# SCH_Extension-Platine-Relais-ESP32-Veth_.net
KiCad netlist of a schematic drawn in EasyEDA
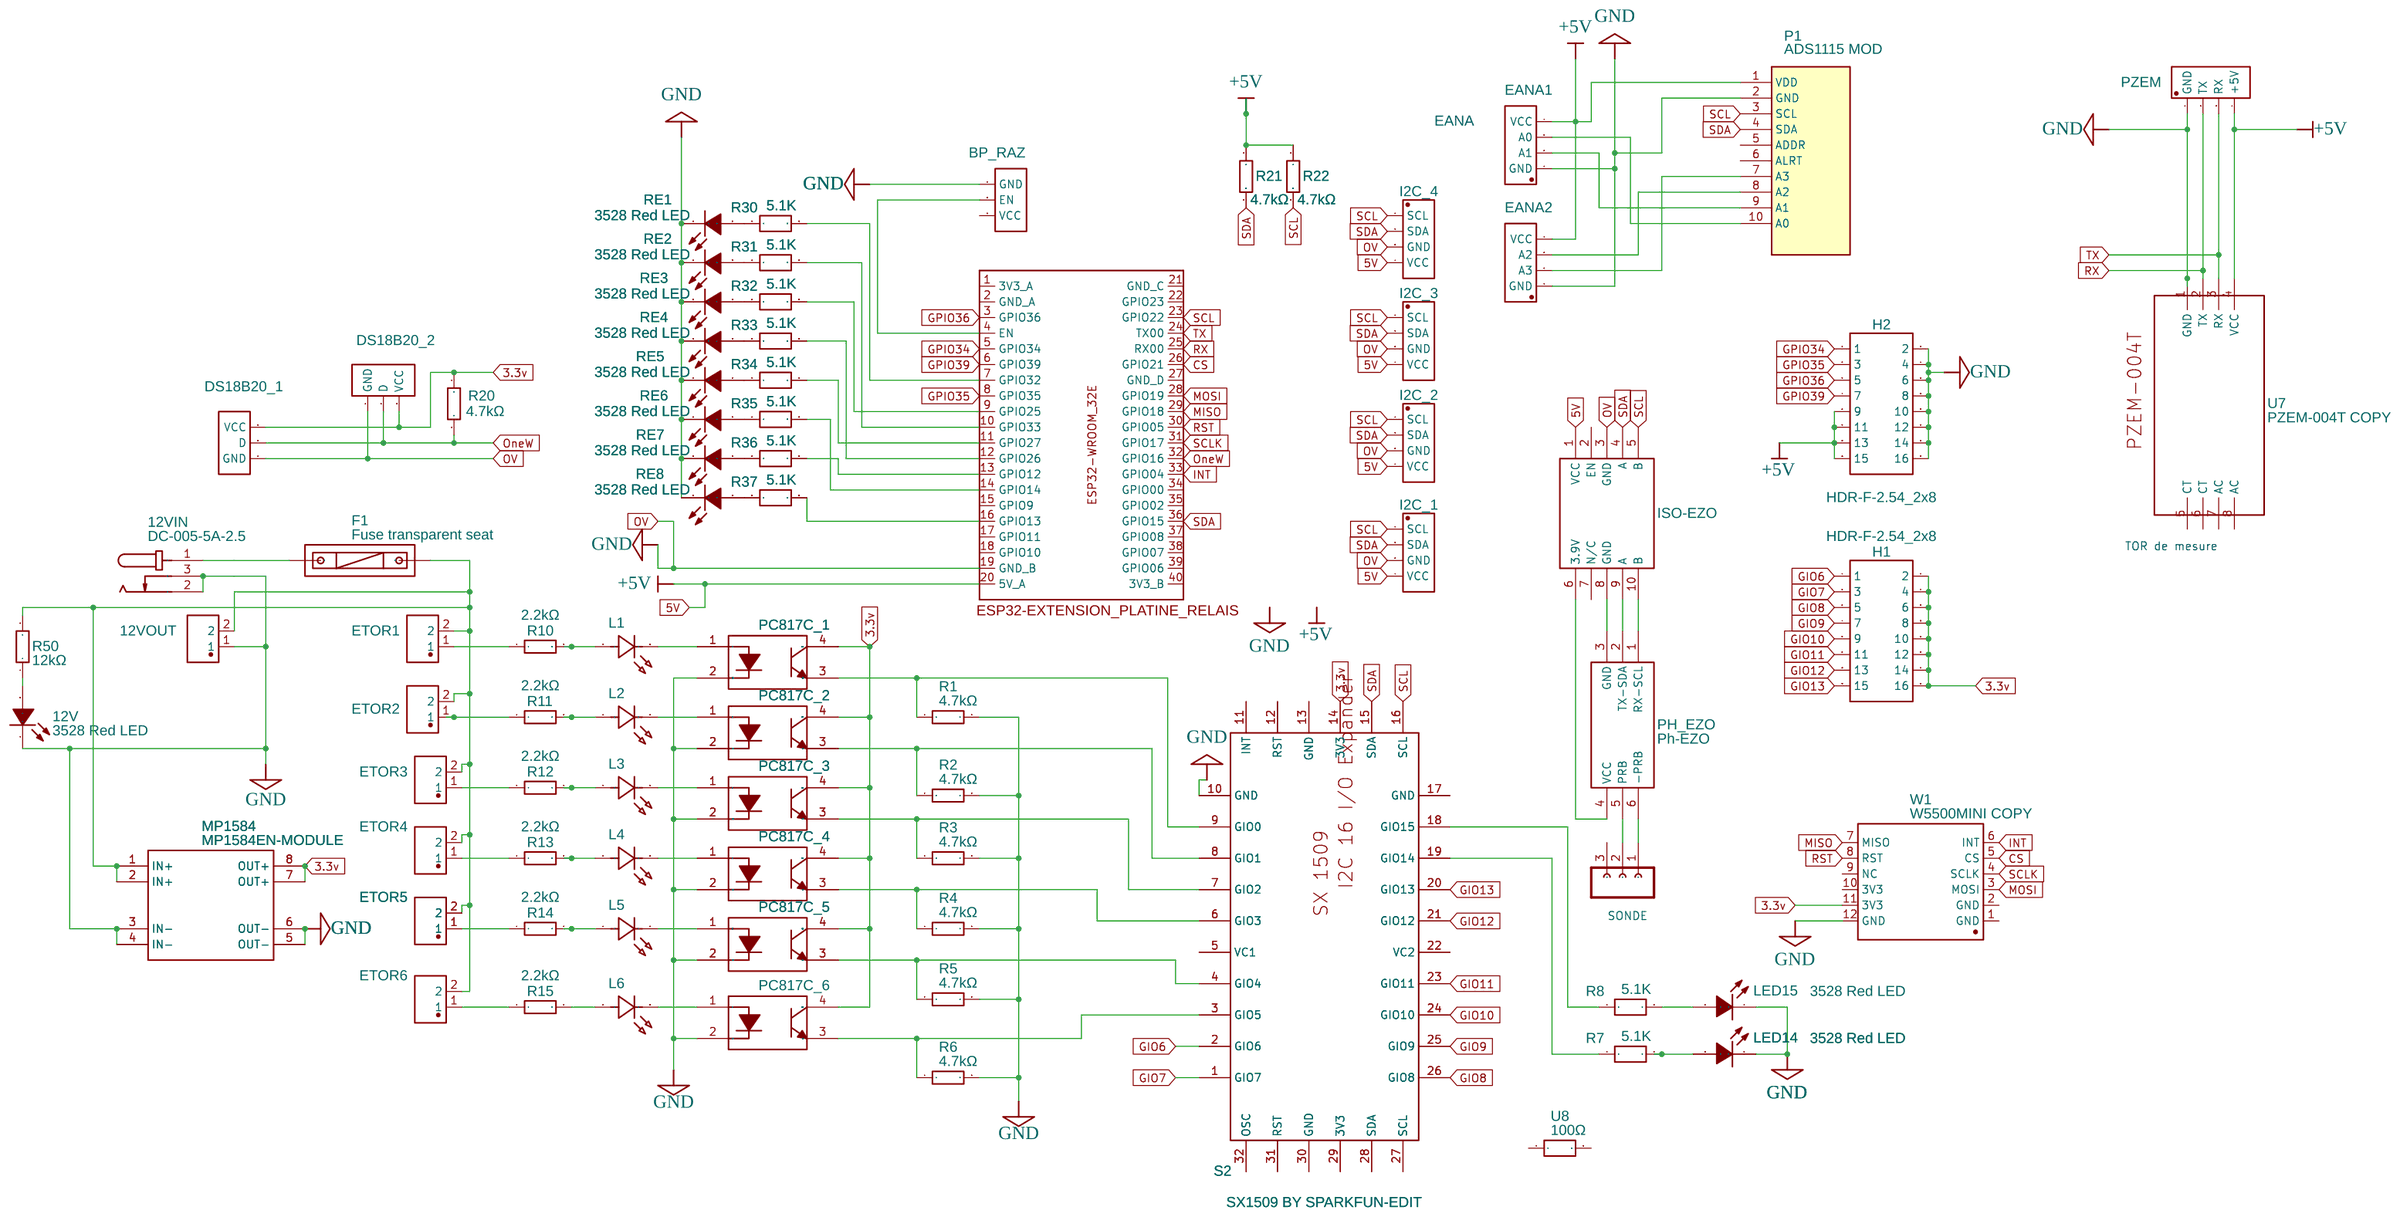
[diagram p0: schematic sheet]

(export (version "E")
  (design (tool "Eeschema 10.0.6"))
  (components
    (comp (ref "12V")
      (value "3528 Red LED")
      (fields (field (name "Manufacturer Part") "3528R (SMT业务专用)"))
      (libsource (lib "") (part "3528 Red LED_2"))
    )
    (comp (ref "12VIN")
      (value "DC-005-5A-2.5")
      (fields (field (name "Manufacturer") "XKB Connectivity(中国星坤)"))
      (libsource (lib "") (part "DC-005-5A-2.5"))
    )
    (comp (ref "12VOUT")
      (value "12V1")
      (fields
        (field (name "Manufacturer Part") "DB128L-5.08-2P-GN-S")
        (field (name "Manufacturer") "DORABO(地博电气)")
      )
      (libsource (lib "") (part "DB128L-5.08-2P_1"))
    )
    (comp (ref "BP_RAZ")
      (value "RAZ")
      (fields (field (name "Manufacturer Part") "Header2.54mm 1*3P") (field (name "Manufacturer") "BOOMELE"))
      (libsource (lib "") (part "Unknown_190_-515"))
    )
    (comp (ref "DS18B20_1")
      (value "DS18B20_1")
      (fields (field (name "Manufacturer Part") "Header2.54mm 1*3P") (field (name "Manufacturer") "BOOMELE"))
      (libsource (lib "") (part "Unknown_-295_-360"))
    )
    (comp (ref "DS18B20_2")
      (value "DS18B20_2")
      (fields (field (name "Manufacturer Part") "Header2.54mm 1*3P") (field (name "Manufacturer") "BOOMELE"))
      (libsource (lib "") (part "Unknown_-205_-395"))
    )
    (comp (ref "EANA1")
      (value "I2C_2")
      (fields
        (field (name "Manufacturer Part") "210S-1*4P L=11.6MMGold-plated black")
        (field (name "Manufacturer") "Ckmtw")
      )
      (libsource (lib "") (part "Unknown_525_-550"))
    )
    (comp (ref "EANA2")
      (value "I2C_2")
      (fields
        (field (name "Manufacturer Part") "210S-1*4P L=11.6MMGold-plated black")
        (field (name "Manufacturer") "Ckmtw")
      )
      (libsource (lib "") (part "Unknown_525_-475"))
    )
    (comp (ref "ETOR1")
      (value "ETOR1")
      (fields
        (field (name "Manufacturer Part") "DB128L-5.08-2P-GN-S")
        (field (name "Manufacturer") "DORABO(地博电气)")
      )
      (libsource (lib "") (part "DB128L-5.08-2P"))
    )
    (comp (ref "ETOR2")
      (value "ETOR1")
      (fields
        (field (name "Manufacturer Part") "DB128L-5.08-2P-GN-S")
        (field (name "Manufacturer") "DORABO(地博电气)")
      )
      (libsource (lib "") (part "DB128L-5.08-2P"))
    )
    (comp (ref "ETOR3")
      (value "ETOR1")
      (fields
        (field (name "Manufacturer Part") "DB128L-5.08-2P-GN-S")
        (field (name "Manufacturer") "DORABO(地博电气)")
      )
      (libsource (lib "") (part "DB128L-5.08-2P"))
    )
    (comp (ref "ETOR4")
      (value "ETOR1")
      (fields
        (field (name "Manufacturer Part") "DB128L-5.08-2P-GN-S")
        (field (name "Manufacturer") "DORABO(地博电气)")
      )
      (libsource (lib "") (part "DB128L-5.08-2P"))
    )
    (comp (ref "ETOR5")
      (value "ETOR1")
      (fields
        (field (name "Manufacturer Part") "DB128L-5.08-2P-GN-S")
        (field (name "Manufacturer") "DORABO(地博电气)")
      )
      (libsource (lib "") (part "DB128L-5.08-2P"))
    )
    (comp (ref "ETOR6")
      (value "ETOR1")
      (fields
        (field (name "Manufacturer Part") "DB128L-5.08-2P-GN-S")
        (field (name "Manufacturer") "DORABO(地博电气)")
      )
      (libsource (lib "") (part "DB128L-5.08-2P"))
    )
    (comp (ref "F1")
      (value "Fuse transparent seat")
      (fields (field (name "Manufacturer Part") "保险丝透明座") (field (name "Manufacturer") "xcfuse(旭程)"))
      (libsource (lib "") (part "Fuse transparent seat"))
    )
    (comp (ref "H1") (value "HDR-F-2.54_2x8") (libsource (lib "") (part "HDR-F-2.54_2x8")))
    (comp (ref "H2") (value "HDR-F-2.54_2x8") (libsource (lib "") (part "HDR-F-2.54_2x8")))
    (comp (ref "I2C_1")
      (value "I2C_2")
      (fields
        (field (name "Manufacturer Part") "210S-1*4P L=11.6MMGold-plated black")
        (field (name "Manufacturer") "Ckmtw")
      )
      (libsource (lib "") (part "Unknown_450_-290"))
    )
    (comp (ref "I2C_2")
      (value "I2C_2")
      (fields
        (field (name "Manufacturer Part") "210S-1*4P L=11.6MMGold-plated black")
        (field (name "Manufacturer") "Ckmtw")
      )
      (libsource (lib "") (part "Unknown_450_-360"))
    )
    (comp (ref "I2C_3")
      (value "I2C_2")
      (fields
        (field (name "Manufacturer Part") "210S-1*4P L=11.6MMGold-plated black")
        (field (name "Manufacturer") "Ckmtw")
      )
      (libsource (lib "") (part "Unknown_450_-425"))
    )
    (comp (ref "I2C_4")
      (value "I2C_2")
      (fields
        (field (name "Manufacturer Part") "210S-1*4P L=11.6MMGold-plated black")
        (field (name "Manufacturer") "Ckmtw")
      )
      (libsource (lib "") (part "Unknown_450_-490"))
    )
    (comp (ref "ISO-EZO") (value "EZO-PH-ISOLATOR") (libsource (lib "") (part "EZO-PH-ISOLATOR")))
    (comp (ref "L1")
      (value "HLMP-4700")
      (fields (field (name "Manufacturer") "Broadcom/AVAGO(安华高)"))
      (libsource (lib "") (part "HLMP-4700"))
    )
    (comp (ref "L2")
      (value "HLMP-4700")
      (fields (field (name "Manufacturer") "Broadcom/AVAGO(安华高)"))
      (libsource (lib "") (part "HLMP-4700"))
    )
    (comp (ref "L3")
      (value "HLMP-4700")
      (fields (field (name "Manufacturer") "Broadcom/AVAGO(安华高)"))
      (libsource (lib "") (part "HLMP-4700"))
    )
    (comp (ref "L4")
      (value "HLMP-4700")
      (fields (field (name "Manufacturer") "Broadcom/AVAGO(安华高)"))
      (libsource (lib "") (part "HLMP-4700"))
    )
    (comp (ref "L5")
      (value "HLMP-4700")
      (fields (field (name "Manufacturer") "Broadcom/AVAGO(安华高)"))
      (libsource (lib "") (part "HLMP-4700"))
    )
    (comp (ref "L6")
      (value "HLMP-4700")
      (fields (field (name "Manufacturer") "Broadcom/AVAGO(安华高)"))
      (libsource (lib "") (part "HLMP-4700"))
    )
    (comp (ref "LED14")
      (value "3528 Red LED")
      (fields (field (name "Manufacturer Part") "3528R (SMT业务专用)"))
      (libsource (lib "") (part "3528 Red LED_1"))
    )
    (comp (ref "LED15")
      (value "3528 Red LED")
      (fields (field (name "Manufacturer Part") "3528R (SMT业务专用)"))
      (libsource (lib "") (part "3528 Red LED_1"))
    )
    (comp (ref "MP1584") (value "MP1584EN-MODULE") (libsource (lib "") (part "MP1584EN-MODULE")))
    (comp (ref "P1") (value "ADS1115 MOD") (libsource (lib "") (part "ADS1115 MOD")))
    (comp (ref "PH_EZO") (value "Ph-EZO") (libsource (lib "") (part "EC-EZO")))
    (comp (ref "PZEM")
      (value "I2C_2")
      (fields
        (field (name "Manufacturer Part") "210S-1*4P L=11.6MMGold-plated black")
        (field (name "Manufacturer") "Ckmtw")
      )
      (libsource (lib "") (part "Unknown_960_-585"))
    )
    (comp (ref "R1")
      (value "4.7kΩ")
      (fields
        (field (name "Manufacturer Part") "MFR0W8F4701A50")
        (field (name "Manufacturer") "UNI-ROYAL(厚声)")
      )
      (libsource (lib "") (part "MFR0W8F4701A50"))
    )
    (comp (ref "R2")
      (value "4.7kΩ")
      (fields
        (field (name "Manufacturer Part") "MFR0W8F4701A50")
        (field (name "Manufacturer") "UNI-ROYAL(厚声)")
      )
      (libsource (lib "") (part "MFR0W8F4701A50"))
    )
    (comp (ref "R3")
      (value "4.7kΩ")
      (fields
        (field (name "Manufacturer Part") "MFR0W8F4701A50")
        (field (name "Manufacturer") "UNI-ROYAL(厚声)")
      )
      (libsource (lib "") (part "MFR0W8F4701A50"))
    )
    (comp (ref "R4")
      (value "4.7kΩ")
      (fields
        (field (name "Manufacturer Part") "MFR0W8F4701A50")
        (field (name "Manufacturer") "UNI-ROYAL(厚声)")
      )
      (libsource (lib "") (part "MFR0W8F4701A50"))
    )
    (comp (ref "R5")
      (value "4.7kΩ")
      (fields
        (field (name "Manufacturer Part") "MFR0W8F4701A50")
        (field (name "Manufacturer") "UNI-ROYAL(厚声)")
      )
      (libsource (lib "") (part "MFR0W8F4701A50"))
    )
    (comp (ref "R6")
      (value "4.7kΩ")
      (fields
        (field (name "Manufacturer Part") "MFR0W8F4701A50")
        (field (name "Manufacturer") "UNI-ROYAL(厚声)")
      )
      (libsource (lib "") (part "MFR0W8F4701A50"))
    )
    (comp (ref "R7") (value "5.1K") (libsource (lib "") (part "R_1206_EU")))
    (comp (ref "R8") (value "5.1K") (libsource (lib "") (part "R_1206_EU")))
    (comp (ref "R10")
      (value "2.2kΩ")
      (fields
        (field (name "Manufacturer Part") "MFR0W8F2201A50")
        (field (name "Manufacturer") "UNI-ROYAL(厚声)")
      )
      (libsource (lib "") (part "MFR0W8F2201A50"))
    )
    (comp (ref "R11")
      (value "2.2kΩ")
      (fields
        (field (name "Manufacturer Part") "MFR0W8F2201A50")
        (field (name "Manufacturer") "UNI-ROYAL(厚声)")
      )
      (libsource (lib "") (part "MFR0W8F2201A50"))
    )
    (comp (ref "R12")
      (value "2.2kΩ")
      (fields
        (field (name "Manufacturer Part") "MFR0W8F2201A50")
        (field (name "Manufacturer") "UNI-ROYAL(厚声)")
      )
      (libsource (lib "") (part "MFR0W8F2201A50"))
    )
    (comp (ref "R13")
      (value "2.2kΩ")
      (fields
        (field (name "Manufacturer Part") "MFR0W8F2201A50")
        (field (name "Manufacturer") "UNI-ROYAL(厚声)")
      )
      (libsource (lib "") (part "MFR0W8F2201A50"))
    )
    (comp (ref "R14")
      (value "2.2kΩ")
      (fields
        (field (name "Manufacturer Part") "MFR0W8F2201A50")
        (field (name "Manufacturer") "UNI-ROYAL(厚声)")
      )
      (libsource (lib "") (part "MFR0W8F2201A50"))
    )
    (comp (ref "R15")
      (value "2.2kΩ")
      (fields
        (field (name "Manufacturer Part") "MFR0W8F2201A50")
        (field (name "Manufacturer") "UNI-ROYAL(厚声)")
      )
      (libsource (lib "") (part "MFR0W8F2201A50"))
    )
    (comp (ref "R20")
      (value "4.7kΩ")
      (fields
        (field (name "Manufacturer Part") "MFR0W8F4701A50")
        (field (name "Manufacturer") "UNI-ROYAL(厚声)")
      )
      (libsource (lib "") (part "MFR0W8F4701A50_1"))
    )
    (comp (ref "R21")
      (value "4.7kΩ")
      (fields
        (field (name "Manufacturer Part") "MFR0W8F4701A50")
        (field (name "Manufacturer") "UNI-ROYAL(厚声)")
      )
      (libsource (lib "") (part "MFR0W8F4701A50_1"))
    )
    (comp (ref "R22")
      (value "4.7kΩ")
      (fields
        (field (name "Manufacturer Part") "MFR0W8F4701A50")
        (field (name "Manufacturer") "UNI-ROYAL(厚声)")
      )
      (libsource (lib "") (part "MFR0W8F4701A50_1"))
    )
    (comp (ref "R30") (value "5.1K") (libsource (lib "") (part "R_1206_EU")))
    (comp (ref "R31") (value "5.1K") (libsource (lib "") (part "R_1206_EU")))
    (comp (ref "R32") (value "5.1K") (libsource (lib "") (part "R_1206_EU")))
    (comp (ref "R33") (value "5.1K") (libsource (lib "") (part "R_1206_EU")))
    (comp (ref "R34") (value "5.1K") (libsource (lib "") (part "R_1206_EU")))
    (comp (ref "R35") (value "5.1K") (libsource (lib "") (part "R_1206_EU")))
    (comp (ref "R36") (value "5.1K") (libsource (lib "") (part "R_1206_EU")))
    (comp (ref "R37") (value "5.1K") (libsource (lib "") (part "R_1206_EU")))
    (comp (ref "R50")
      (value "12kΩ")
      (fields
        (field (name "Manufacturer Part") "MFR0W8F2201A50")
        (field (name "Manufacturer") "UNI-ROYAL(厚声)")
      )
      (libsource (lib "") (part "MFR0W8F2201A50_1"))
    )
    (comp (ref "RE1")
      (value "3528 Red LED")
      (fields (field (name "Manufacturer Part") "3528R (SMT业务专用)"))
      (libsource (lib "") (part "3528 Red LED"))
    )
    (comp (ref "RE2")
      (value "3528 Red LED")
      (fields (field (name "Manufacturer Part") "3528R (SMT业务专用)"))
      (libsource (lib "") (part "3528 Red LED"))
    )
    (comp (ref "RE3")
      (value "3528 Red LED")
      (fields (field (name "Manufacturer Part") "3528R (SMT业务专用)"))
      (libsource (lib "") (part "3528 Red LED"))
    )
    (comp (ref "RE4")
      (value "3528 Red LED")
      (fields (field (name "Manufacturer Part") "3528R (SMT业务专用)"))
      (libsource (lib "") (part "3528 Red LED"))
    )
    (comp (ref "RE5")
      (value "3528 Red LED")
      (fields (field (name "Manufacturer Part") "3528R (SMT业务专用)"))
      (libsource (lib "") (part "3528 Red LED"))
    )
    (comp (ref "RE6")
      (value "3528 Red LED")
      (fields (field (name "Manufacturer Part") "3528R (SMT业务专用)"))
      (libsource (lib "") (part "3528 Red LED"))
    )
    (comp (ref "RE7")
      (value "3528 Red LED")
      (fields (field (name "Manufacturer Part") "3528R (SMT业务专用)"))
      (libsource (lib "") (part "3528 Red LED"))
    )
    (comp (ref "RE8")
      (value "3528 Red LED")
      (fields (field (name "Manufacturer Part") "3528R (SMT业务专用)"))
      (libsource (lib "") (part "3528 Red LED"))
    )
    (comp (ref "S2")
      (value "SX1509 BY SPARKFUN-EDIT")
      (fields (field (name "Manufacturer Part") "SX1509") (field (name "Manufacturer") "SPARkFUN"))
      (libsource (lib "") (part "SX1509 BY SPARKFUN-EDIT"))
    )
    (comp (ref "SONDE") (value "FE03-1\"") (libsource (lib "") (part "Unknown_585_-75")))
    (comp (ref "U$1") (value "ESP32-PLATINE_RELAIS") (libsource (lib "") (part "Unknown_245_-360")))
    (comp (ref "U1")
      (value "PC817C_1")
      (fields (field (name "Manufacturer Part") "PC817C") (field (name "Manufacturer") "Slkor(萨科微)"))
      (libsource (lib "") (part "PC817C_C5186572"))
    )
    (comp (ref "U2")
      (value "PC817C_2")
      (fields (field (name "Manufacturer Part") "PC817C") (field (name "Manufacturer") "Slkor(萨科微)"))
      (libsource (lib "") (part "PC817C_C5186572"))
    )
    (comp (ref "U3")
      (value "PC817C_3")
      (fields (field (name "Manufacturer Part") "PC817C") (field (name "Manufacturer") "Slkor(萨科微)"))
      (libsource (lib "") (part "PC817C_C5186572"))
    )
    (comp (ref "U4")
      (value "PC817C_4")
      (fields (field (name "Manufacturer Part") "PC817C") (field (name "Manufacturer") "Slkor(萨科微)"))
      (libsource (lib "") (part "PC817C_C5186572"))
    )
    (comp (ref "U5")
      (value "PC817C_5")
      (fields (field (name "Manufacturer Part") "PC817C") (field (name "Manufacturer") "Slkor(萨科微)"))
      (libsource (lib "") (part "PC817C_C5186572"))
    )
    (comp (ref "U6")
      (value "PC817C_6")
      (fields (field (name "Manufacturer Part") "PC817C") (field (name "Manufacturer") "Slkor(萨科微)"))
      (libsource (lib "") (part "PC817C_C5186572"))
    )
    (comp (ref "U7") (value "PZEM-004T COPY") (libsource (lib "") (part "PZEM-004T COPY")))
    (comp (ref "U8")
      (value "100Ω")
      (fields (field (name "Manufacturer Part") "FRC1812J101 TS") (field (name "Manufacturer") "FOJAN(富捷)"))
      (libsource (lib "") (part "FRC1812J101 TS"))
    )
    (comp (ref "W1") (value "W5500MINI COPY") (libsource (lib "") (part "W5500MINI")))
  )
  (nets
    (net (code "1") (name "3.3v") (class "Default")
      (node (ref "DS18B20_1") (pin "3") (pinfunction "VCC_3") (pintype "input"))
      (node (ref "DS18B20_2") (pin "3") (pinfunction "VCC_3") (pintype "input"))
      (node (ref "H1") (pin "10") (pinfunction "10_10") (pintype "input"))
      (node (ref "H1") (pin "12") (pinfunction "12_12") (pintype "input"))
      (node (ref "H1") (pin "14") (pinfunction "14_14") (pintype "input"))
      (node (ref "H1") (pin "16") (pinfunction "16_16") (pintype "input"))
      (node (ref "H1") (pin "2") (pinfunction "2_2") (pintype "input"))
      (node (ref "H1") (pin "4") (pinfunction "4_4") (pintype "input"))
      (node (ref "H1") (pin "6") (pinfunction "6_6") (pintype "input"))
      (node (ref "H1") (pin "8") (pinfunction "8_8") (pintype "input"))
      (node (ref "MP1584") (pin "7") (pinfunction "OUT+_7") (pintype "unspecified"))
      (node (ref "MP1584") (pin "8") (pinfunction "OUT+_8") (pintype "unspecified"))
      (node (ref "R20") (pin "1") (pinfunction "1_1") (pintype "input"))
      (node (ref "S2") (pin "14") (pinfunction "3V3_14") (pintype "unspecified"))
      (node (ref "U1") (pin "4") (pinfunction "Collector_4") (pintype "unspecified"))
      (node (ref "U2") (pin "4") (pinfunction "Collector_4") (pintype "unspecified"))
      (node (ref "U3") (pin "4") (pinfunction "Collector_4") (pintype "unspecified"))
      (node (ref "U4") (pin "4") (pinfunction "Collector_4") (pintype "unspecified"))
      (node (ref "U5") (pin "4") (pinfunction "Collector_4") (pintype "unspecified"))
      (node (ref "U6") (pin "4") (pinfunction "Collector_4") (pintype "unspecified"))
      (node (ref "W1") (pin "11") (pinfunction "3V3_11") (pintype "unspecified"))
    )
    (net (code "2") (name "5V") (class "Default")
      (node (ref "EANA1") (pin "4") (pinfunction "VCC_4") (pintype "unspecified"))
      (node (ref "EANA2") (pin "4") (pinfunction "VCC_4") (pintype "unspecified"))
      (node (ref "H2") (pin "11") (pinfunction "11_11") (pintype "input"))
      (node (ref "H2") (pin "13") (pinfunction "13_13") (pintype "input"))
      (node (ref "H2") (pin "15") (pinfunction "15_15") (pintype "input"))
      (node (ref "H2") (pin "9") (pinfunction "9_9") (pintype "input"))
      (node (ref "I2C_1") (pin "4") (pinfunction "VCC_4") (pintype "unspecified"))
      (node (ref "I2C_2") (pin "4") (pinfunction "VCC_4") (pintype "unspecified"))
      (node (ref "I2C_3") (pin "4") (pinfunction "VCC_4") (pintype "unspecified"))
      (node (ref "I2C_4") (pin "4") (pinfunction "VCC_4") (pintype "unspecified"))
      (node (ref "ISO-EZO") (pin "1") (pinfunction "VCC_1") (pintype "unspecified"))
      (node (ref "P1") (pin "1") (pinfunction "VDD_1") (pintype "unspecified"))
      (node (ref "PZEM") (pin "4") (pinfunction "+5V_4") (pintype "unspecified"))
      (node (ref "R21") (pin "1") (pinfunction "1_1") (pintype "input"))
      (node (ref "R22") (pin "1") (pinfunction "1_1") (pintype "input"))
      (node (ref "U$1") (pin "20") (pinfunction "5V_A_20") (pintype "bidirectional"))
      (node (ref "U7") (pin "4") (pinfunction "VCC_4") (pintype "unspecified"))
    )
    (net (code "3") (name "CS") (class "Default")
      (node (ref "U$1") (pin "26") (pinfunction "GPIO21_26") (pintype "bidirectional"))
      (node (ref "W1") (pin "5") (pinfunction "CS_5") (pintype "unspecified"))
    )
    (net (code "4") (name "GIO6") (class "Default")
      (node (ref "H1") (pin "1") (pinfunction "1_1") (pintype "input"))
      (node (ref "S2") (pin "2") (pinfunction "GIO6_2") (pintype "unspecified"))
    )
    (net (code "5") (name "GIO7") (class "Default")
      (node (ref "H1") (pin "3") (pinfunction "3_3") (pintype "input"))
      (node (ref "S2") (pin "1") (pinfunction "GIO7_1") (pintype "unspecified"))
    )
    (net (code "6") (name "GIO8") (class "Default")
      (node (ref "H1") (pin "5") (pinfunction "5_5") (pintype "input"))
      (node (ref "S2") (pin "26") (pinfunction "GIO8_26") (pintype "unspecified"))
    )
    (net (code "7") (name "GIO9") (class "Default")
      (node (ref "H1") (pin "7") (pinfunction "7_7") (pintype "input"))
      (node (ref "S2") (pin "25") (pinfunction "GIO9_25") (pintype "unspecified"))
    )
    (net (code "8") (name "GIO10") (class "Default")
      (node (ref "H1") (pin "9") (pinfunction "9_9") (pintype "input"))
      (node (ref "S2") (pin "24") (pinfunction "GIO10_24") (pintype "unspecified"))
    )
    (net (code "9") (name "GIO11") (class "Default")
      (node (ref "H1") (pin "11") (pinfunction "11_11") (pintype "input"))
      (node (ref "S2") (pin "23") (pinfunction "GIO11_23") (pintype "unspecified"))
    )
    (net (code "10") (name "GIO12") (class "Default")
      (node (ref "H1") (pin "13") (pinfunction "13_13") (pintype "input"))
      (node (ref "S2") (pin "21") (pinfunction "GIO12_21") (pintype "unspecified"))
    )
    (net (code "11") (name "GIO13") (class "Default")
      (node (ref "H1") (pin "15") (pinfunction "15_15") (pintype "input"))
      (node (ref "S2") (pin "20") (pinfunction "GIO13_20") (pintype "unspecified"))
    )
    (net (code "12") (name "GPIO34") (class "Default")
      (node (ref "H2") (pin "1") (pinfunction "1_1") (pintype "input"))
      (node (ref "U$1") (pin "5") (pinfunction "GPIO34_5") (pintype "bidirectional"))
    )
    (net (code "13") (name "GPIO35") (class "Default")
      (node (ref "H2") (pin "3") (pinfunction "3_3") (pintype "input"))
      (node (ref "U$1") (pin "8") (pinfunction "GPIO35_8") (pintype "bidirectional"))
    )
    (net (code "14") (name "GPIO36") (class "Default")
      (node (ref "H2") (pin "5") (pinfunction "5_5") (pintype "input"))
      (node (ref "U$1") (pin "3") (pinfunction "GPIO36_3") (pintype "bidirectional"))
    )
    (net (code "15") (name "GPIO39") (class "Default")
      (node (ref "H2") (pin "7") (pinfunction "7_7") (pintype "input"))
      (node (ref "U$1") (pin "6") (pinfunction "GPIO39_6") (pintype "bidirectional"))
    )
    (net (code "16") (name "INT") (class "Default")
      (node (ref "U$1") (pin "33") (pinfunction "GPIO04_33") (pintype "bidirectional"))
      (node (ref "W1") (pin "6") (pinfunction "INT_6") (pintype "unspecified"))
    )
    (net (code "17") (name "MISO") (class "Default")
      (node (ref "U$1") (pin "29") (pinfunction "GPIO18_29") (pintype "bidirectional"))
      (node (ref "W1") (pin "7") (pinfunction "MISO_7") (pintype "unspecified"))
    )
    (net (code "18") (name "MOSI") (class "Default")
      (node (ref "U$1") (pin "28") (pinfunction "GPIO19_28") (pintype "bidirectional"))
      (node (ref "W1") (pin "3") (pinfunction "MOSI_3") (pintype "unspecified"))
    )
    (net (code "19") (name "Net-(12V-A)") (class "Default")
      (node (ref "12V") (pin "2") (pinfunction "A_2") (pintype "unspecified"))
      (node (ref "R50") (pin "1") (pinfunction "1_1") (pintype "input"))
    )
    (net (code "20") (name "Net-(12VIN-Pad1)") (class "Default")
      (node (ref "12VIN") (pin "1") (pinfunction "1_1") (pintype "unspecified"))
      (node (ref "F1") (pin "1") (pinfunction "1_1") (pintype "unspecified"))
    )
    (net (code "21") (name "Net-(12VOUT-Pad2)") (class "Default")
      (node (ref "12VOUT") (pin "2") (pinfunction "2_2") (pintype "unspecified"))
      (node (ref "ETOR1") (pin "2") (pinfunction "2_2") (pintype "unspecified"))
      (node (ref "ETOR2") (pin "2") (pinfunction "2_2") (pintype "unspecified"))
      (node (ref "ETOR3") (pin "2") (pinfunction "2_2") (pintype "unspecified"))
      (node (ref "ETOR4") (pin "2") (pinfunction "2_2") (pintype "unspecified"))
      (node (ref "ETOR5") (pin "2") (pinfunction "2_2") (pintype "unspecified"))
      (node (ref "ETOR6") (pin "2") (pinfunction "2_2") (pintype "unspecified"))
      (node (ref "F1") (pin "2") (pinfunction "2_2") (pintype "unspecified"))
      (node (ref "MP1584") (pin "1") (pinfunction "IN+_1") (pintype "unspecified"))
      (node (ref "MP1584") (pin "2") (pinfunction "IN+_2") (pintype "unspecified"))
      (node (ref "R50") (pin "2") (pinfunction "2_2") (pintype "input"))
    )
    (net (code "22") (name "Net-(BP_RAZ-EN)") (class "Default")
      (node (ref "BP_RAZ") (pin "2") (pinfunction "EN_2") (pintype "input"))
      (node (ref "U$1") (pin "4") (pinfunction "EN_4") (pintype "bidirectional"))
    )
    (net (code "23") (name "Net-(EANA1-A0)") (class "Default")
      (node (ref "EANA1") (pin "3") (pinfunction "A0_3") (pintype "unspecified"))
      (node (ref "P1") (pin "10") (pinfunction "A0_10") (pintype "unspecified"))
    )
    (net (code "24") (name "Net-(EANA1-A1)") (class "Default")
      (node (ref "EANA1") (pin "2") (pinfunction "A1_2") (pintype "unspecified"))
      (node (ref "P1") (pin "9") (pinfunction "A1_9") (pintype "unspecified"))
    )
    (net (code "25") (name "Net-(EANA2-A2)") (class "Default")
      (node (ref "EANA2") (pin "3") (pinfunction "A2_3") (pintype "unspecified"))
      (node (ref "P1") (pin "8") (pinfunction "A2_8") (pintype "unspecified"))
    )
    (net (code "26") (name "Net-(EANA2-A3)") (class "Default")
      (node (ref "EANA2") (pin "2") (pinfunction "A3_2") (pintype "unspecified"))
      (node (ref "P1") (pin "7") (pinfunction "A3_7") (pintype "unspecified"))
    )
    (net (code "27") (name "Net-(ETOR1-Pad1)") (class "Default")
      (node (ref "ETOR1") (pin "1") (pinfunction "1_1") (pintype "unspecified"))
      (node (ref "R10") (pin "1") (pinfunction "1_1") (pintype "input"))
    )
    (net (code "28") (name "Net-(ETOR2-Pad1)") (class "Default")
      (node (ref "ETOR2") (pin "1") (pinfunction "1_1") (pintype "unspecified"))
      (node (ref "R11") (pin "1") (pinfunction "1_1") (pintype "input"))
    )
    (net (code "29") (name "Net-(ETOR3-Pad1)") (class "Default")
      (node (ref "ETOR3") (pin "1") (pinfunction "1_1") (pintype "unspecified"))
      (node (ref "R12") (pin "1") (pinfunction "1_1") (pintype "input"))
    )
    (net (code "30") (name "Net-(ETOR4-Pad1)") (class "Default")
      (node (ref "ETOR4") (pin "1") (pinfunction "1_1") (pintype "unspecified"))
      (node (ref "R13") (pin "1") (pinfunction "1_1") (pintype "input"))
    )
    (net (code "31") (name "Net-(ETOR5-Pad1)") (class "Default")
      (node (ref "ETOR5") (pin "1") (pinfunction "1_1") (pintype "unspecified"))
      (node (ref "R14") (pin "1") (pinfunction "1_1") (pintype "input"))
    )
    (net (code "32") (name "Net-(ETOR6-Pad1)") (class "Default")
      (node (ref "ETOR6") (pin "1") (pinfunction "1_1") (pintype "unspecified"))
      (node (ref "R15") (pin "1") (pinfunction "1_1") (pintype "input"))
    )
    (net (code "33") (name "Net-(ISO-EZO-3.9V)") (class "Default")
      (node (ref "ISO-EZO") (pin "6") (pinfunction "3.9V_6") (pintype "unspecified"))
      (node (ref "PH_EZO") (pin "4") (pinfunction "VCC_4") (pintype "unspecified"))
    )
    (net (code "34") (name "Net-(L1-A)") (class "Default")
      (node (ref "L1") (pin "1") (pinfunction "A_1") (pintype "unspecified"))
      (node (ref "R10") (pin "2") (pinfunction "2_2") (pintype "input"))
    )
    (net (code "35") (name "Net-(L1-K)") (class "Default")
      (node (ref "L1") (pin "2") (pinfunction "K_2") (pintype "unspecified"))
      (node (ref "U1") (pin "1") (pinfunction "Anode_1") (pintype "unspecified"))
    )
    (net (code "36") (name "Net-(L2-A)") (class "Default")
      (node (ref "L2") (pin "1") (pinfunction "A_1") (pintype "unspecified"))
      (node (ref "R11") (pin "2") (pinfunction "2_2") (pintype "input"))
    )
    (net (code "37") (name "Net-(L2-K)") (class "Default")
      (node (ref "L2") (pin "2") (pinfunction "K_2") (pintype "unspecified"))
      (node (ref "U2") (pin "1") (pinfunction "Anode_1") (pintype "unspecified"))
    )
    (net (code "38") (name "Net-(L3-A)") (class "Default")
      (node (ref "L3") (pin "1") (pinfunction "A_1") (pintype "unspecified"))
      (node (ref "R12") (pin "2") (pinfunction "2_2") (pintype "input"))
    )
    (net (code "39") (name "Net-(L3-K)") (class "Default")
      (node (ref "L3") (pin "2") (pinfunction "K_2") (pintype "unspecified"))
      (node (ref "U3") (pin "1") (pinfunction "Anode_1") (pintype "unspecified"))
    )
    (net (code "40") (name "Net-(L4-A)") (class "Default")
      (node (ref "L4") (pin "1") (pinfunction "A_1") (pintype "unspecified"))
      (node (ref "R13") (pin "2") (pinfunction "2_2") (pintype "input"))
    )
    (net (code "41") (name "Net-(L4-K)") (class "Default")
      (node (ref "L4") (pin "2") (pinfunction "K_2") (pintype "unspecified"))
      (node (ref "U4") (pin "1") (pinfunction "Anode_1") (pintype "unspecified"))
    )
    (net (code "42") (name "Net-(L5-A)") (class "Default")
      (node (ref "L5") (pin "1") (pinfunction "A_1") (pintype "unspecified"))
      (node (ref "R14") (pin "2") (pinfunction "2_2") (pintype "input"))
    )
    (net (code "43") (name "Net-(L5-K)") (class "Default")
      (node (ref "L5") (pin "2") (pinfunction "K_2") (pintype "unspecified"))
      (node (ref "U5") (pin "1") (pinfunction "Anode_1") (pintype "unspecified"))
    )
    (net (code "44") (name "Net-(L6-A)") (class "Default")
      (node (ref "L6") (pin "1") (pinfunction "A_1") (pintype "unspecified"))
      (node (ref "R15") (pin "2") (pinfunction "2_2") (pintype "input"))
    )
    (net (code "45") (name "Net-(L6-K)") (class "Default")
      (node (ref "L6") (pin "2") (pinfunction "K_2") (pintype "unspecified"))
      (node (ref "U6") (pin "1") (pinfunction "Anode_1") (pintype "unspecified"))
    )
    (net (code "46") (name "Net-(LED14-A)") (class "Default")
      (node (ref "LED14") (pin "2") (pinfunction "A_2") (pintype "unspecified"))
      (node (ref "R7") (pin "2") (pinfunction "2_2") (pintype "unspecified"))
    )
    (net (code "47") (name "Net-(LED15-A)") (class "Default")
      (node (ref "LED15") (pin "2") (pinfunction "A_2") (pintype "unspecified"))
      (node (ref "R8") (pin "2") (pinfunction "2_2") (pintype "unspecified"))
    )
    (net (code "48") (name "Net-(PH_EZO--PRB)") (class "Default")
      (node (ref "PH_EZO") (pin "6") (pinfunction "-PRB_6") (pintype "unspecified"))
      (node (ref "SONDE") (pin "1") (pinfunction "1_1") (pintype "bidirectional"))
    )
    (net (code "49") (name "Net-(PH_EZO-GND)") (class "Default")
      (node (ref "ISO-EZO") (pin "8") (pinfunction "GND_8") (pintype "unspecified"))
      (node (ref "PH_EZO") (pin "3") (pinfunction "GND_3") (pintype "unspecified"))
    )
    (net (code "50") (name "Net-(PH_EZO-PRB)") (class "Default")
      (node (ref "PH_EZO") (pin "5") (pinfunction "PRB_5") (pintype "unspecified"))
      (node (ref "SONDE") (pin "2") (pinfunction "2_2") (pintype "bidirectional"))
    )
    (net (code "51") (name "Net-(PH_EZO-RX-SCL)") (class "Default")
      (node (ref "ISO-EZO") (pin "10") (pinfunction "B_10") (pintype "unspecified"))
      (node (ref "PH_EZO") (pin "1") (pinfunction "RX-SCL_1") (pintype "unspecified"))
    )
    (net (code "52") (name "Net-(PH_EZO-TX-SDA)") (class "Default")
      (node (ref "ISO-EZO") (pin "9") (pinfunction "A_9") (pintype "unspecified"))
      (node (ref "PH_EZO") (pin "2") (pinfunction "TX-SDA_2") (pintype "unspecified"))
    )
    (net (code "53") (name "Net-(RE1-A)") (class "Default")
      (node (ref "R30") (pin "1") (pinfunction "1_1") (pintype "unspecified"))
      (node (ref "RE1") (pin "2") (pinfunction "A_2") (pintype "unspecified"))
    )
    (net (code "54") (name "Net-(RE2-A)") (class "Default")
      (node (ref "R31") (pin "1") (pinfunction "1_1") (pintype "unspecified"))
      (node (ref "RE2") (pin "2") (pinfunction "A_2") (pintype "unspecified"))
    )
    (net (code "55") (name "Net-(RE3-A)") (class "Default")
      (node (ref "R32") (pin "1") (pinfunction "1_1") (pintype "unspecified"))
      (node (ref "RE3") (pin "2") (pinfunction "A_2") (pintype "unspecified"))
    )
    (net (code "56") (name "Net-(RE4-A)") (class "Default")
      (node (ref "R33") (pin "1") (pinfunction "1_1") (pintype "unspecified"))
      (node (ref "RE4") (pin "2") (pinfunction "A_2") (pintype "unspecified"))
    )
    (net (code "57") (name "Net-(RE5-A)") (class "Default")
      (node (ref "R34") (pin "1") (pinfunction "1_1") (pintype "unspecified"))
      (node (ref "RE5") (pin "2") (pinfunction "A_2") (pintype "unspecified"))
    )
    (net (code "58") (name "Net-(RE6-A)") (class "Default")
      (node (ref "R35") (pin "1") (pinfunction "1_1") (pintype "unspecified"))
      (node (ref "RE6") (pin "2") (pinfunction "A_2") (pintype "unspecified"))
    )
    (net (code "59") (name "Net-(RE7-A)") (class "Default")
      (node (ref "R36") (pin "1") (pinfunction "1_1") (pintype "unspecified"))
      (node (ref "RE7") (pin "2") (pinfunction "A_2") (pintype "unspecified"))
    )
    (net (code "60") (name "Net-(RE8-A)") (class "Default")
      (node (ref "R37") (pin "1") (pinfunction "1_1") (pintype "unspecified"))
      (node (ref "RE8") (pin "2") (pinfunction "A_2") (pintype "unspecified"))
    )
    (net (code "61") (name "Net-(S2-GIO0)") (class "Default")
      (node (ref "R1") (pin "1") (pinfunction "1_1") (pintype "input"))
      (node (ref "S2") (pin "9") (pinfunction "GIO0_9") (pintype "unspecified"))
      (node (ref "U1") (pin "3") (pinfunction "Emitter_3") (pintype "unspecified"))
    )
    (net (code "62") (name "Net-(S2-GIO1)") (class "Default")
      (node (ref "R2") (pin "1") (pinfunction "1_1") (pintype "input"))
      (node (ref "S2") (pin "8") (pinfunction "GIO1_8") (pintype "unspecified"))
      (node (ref "U2") (pin "3") (pinfunction "Emitter_3") (pintype "unspecified"))
    )
    (net (code "63") (name "Net-(S2-GIO2)") (class "Default")
      (node (ref "R3") (pin "1") (pinfunction "1_1") (pintype "input"))
      (node (ref "S2") (pin "7") (pinfunction "GIO2_7") (pintype "unspecified"))
      (node (ref "U3") (pin "3") (pinfunction "Emitter_3") (pintype "unspecified"))
    )
    (net (code "64") (name "Net-(S2-GIO3)") (class "Default")
      (node (ref "R4") (pin "1") (pinfunction "1_1") (pintype "input"))
      (node (ref "S2") (pin "6") (pinfunction "GIO3_6") (pintype "unspecified"))
      (node (ref "U4") (pin "3") (pinfunction "Emitter_3") (pintype "unspecified"))
    )
    (net (code "65") (name "Net-(S2-GIO4)") (class "Default")
      (node (ref "R5") (pin "1") (pinfunction "1_1") (pintype "input"))
      (node (ref "S2") (pin "4") (pinfunction "GIO4_4") (pintype "unspecified"))
      (node (ref "U5") (pin "3") (pinfunction "Emitter_3") (pintype "unspecified"))
    )
    (net (code "66") (name "Net-(S2-GIO5)") (class "Default")
      (node (ref "R6") (pin "1") (pinfunction "1_1") (pintype "input"))
      (node (ref "S2") (pin "3") (pinfunction "GIO5_3") (pintype "unspecified"))
      (node (ref "U6") (pin "3") (pinfunction "Emitter_3") (pintype "unspecified"))
    )
    (net (code "67") (name "Net-(S2-GIO14)") (class "Default")
      (node (ref "R7") (pin "1") (pinfunction "1_1") (pintype "unspecified"))
      (node (ref "S2") (pin "19") (pinfunction "GIO14_19") (pintype "unspecified"))
    )
    (net (code "68") (name "Net-(S2-GIO15)") (class "Default")
      (node (ref "R8") (pin "1") (pinfunction "1_1") (pintype "unspecified"))
      (node (ref "S2") (pin "18") (pinfunction "GIO15_18") (pintype "unspecified"))
    )
    (net (code "69") (name "Net-(U$1-GPIO12)") (class "Default")
      (node (ref "R36") (pin "2") (pinfunction "2_2") (pintype "unspecified"))
      (node (ref "U$1") (pin "13") (pinfunction "GPIO12_13") (pintype "bidirectional"))
    )
    (net (code "70") (name "Net-(U$1-GPIO13)") (class "Default")
      (node (ref "R37") (pin "2") (pinfunction "2_2") (pintype "unspecified"))
      (node (ref "U$1") (pin "16") (pinfunction "GPIO13_16") (pintype "bidirectional"))
    )
    (net (code "71") (name "Net-(U$1-GPIO14)") (class "Default")
      (node (ref "R35") (pin "2") (pinfunction "2_2") (pintype "unspecified"))
      (node (ref "U$1") (pin "14") (pinfunction "GPIO14_14") (pintype "bidirectional"))
    )
    (net (code "72") (name "Net-(U$1-GPIO25)") (class "Default")
      (node (ref "R32") (pin "2") (pinfunction "2_2") (pintype "unspecified"))
      (node (ref "U$1") (pin "9") (pinfunction "GPIO25_9") (pintype "bidirectional"))
    )
    (net (code "73") (name "Net-(U$1-GPIO26)") (class "Default")
      (node (ref "R33") (pin "2") (pinfunction "2_2") (pintype "unspecified"))
      (node (ref "U$1") (pin "12") (pinfunction "GPIO26_12") (pintype "bidirectional"))
    )
    (net (code "74") (name "Net-(U$1-GPIO27)") (class "Default")
      (node (ref "R34") (pin "2") (pinfunction "2_2") (pintype "unspecified"))
      (node (ref "U$1") (pin "11") (pinfunction "GPIO27_11") (pintype "bidirectional"))
    )
    (net (code "75") (name "Net-(U$1-GPIO32)") (class "Default")
      (node (ref "R30") (pin "2") (pinfunction "2_2") (pintype "unspecified"))
      (node (ref "U$1") (pin "7") (pinfunction "GPIO32_7") (pintype "bidirectional"))
    )
    (net (code "76") (name "Net-(U$1-GPIO33)") (class "Default")
      (node (ref "R31") (pin "2") (pinfunction "2_2") (pintype "unspecified"))
      (node (ref "U$1") (pin "10") (pinfunction "GPIO33_10") (pintype "bidirectional"))
    )
    (net (code "77") (name "OV") (class "Default")
      (node (ref "12V") (pin "1") (pinfunction "K_1") (pintype "unspecified"))
      (node (ref "12VIN") (pin "2") (pinfunction "2_2") (pintype "unspecified"))
      (node (ref "12VIN") (pin "3") (pinfunction "3_3") (pintype "unspecified"))
      (node (ref "12VOUT") (pin "1") (pinfunction "1_1") (pintype "unspecified"))
      (node (ref "BP_RAZ") (pin "1") (pinfunction "GND_1") (pintype "input"))
      (node (ref "DS18B20_1") (pin "1") (pinfunction "GND_1") (pintype "input"))
      (node (ref "DS18B20_2") (pin "1") (pinfunction "GND_1") (pintype "input"))
      (node (ref "EANA1") (pin "1") (pinfunction "GND_1") (pintype "unspecified"))
      (node (ref "EANA2") (pin "1") (pinfunction "GND_1") (pintype "unspecified"))
      (node (ref "H2") (pin "10") (pinfunction "10_10") (pintype "input"))
      (node (ref "H2") (pin "12") (pinfunction "12_12") (pintype "input"))
      (node (ref "H2") (pin "14") (pinfunction "14_14") (pintype "input"))
      (node (ref "H2") (pin "16") (pinfunction "16_16") (pintype "input"))
      (node (ref "H2") (pin "2") (pinfunction "2_2") (pintype "input"))
      (node (ref "H2") (pin "4") (pinfunction "4_4") (pintype "input"))
      (node (ref "H2") (pin "6") (pinfunction "6_6") (pintype "input"))
      (node (ref "H2") (pin "8") (pinfunction "8_8") (pintype "input"))
      (node (ref "I2C_1") (pin "3") (pinfunction "GND_3") (pintype "unspecified"))
      (node (ref "I2C_2") (pin "3") (pinfunction "GND_3") (pintype "unspecified"))
      (node (ref "I2C_3") (pin "3") (pinfunction "GND_3") (pintype "unspecified"))
      (node (ref "I2C_4") (pin "3") (pinfunction "GND_3") (pintype "unspecified"))
      (node (ref "ISO-EZO") (pin "3") (pinfunction "GND_3") (pintype "unspecified"))
      (node (ref "LED14") (pin "1") (pinfunction "K_1") (pintype "unspecified"))
      (node (ref "LED15") (pin "1") (pinfunction "K_1") (pintype "unspecified"))
      (node (ref "MP1584") (pin "3") (pinfunction "IN-_3") (pintype "unspecified"))
      (node (ref "MP1584") (pin "4") (pinfunction "IN-_4") (pintype "unspecified"))
      (node (ref "MP1584") (pin "5") (pinfunction "OUT-_5") (pintype "unspecified"))
      (node (ref "MP1584") (pin "6") (pinfunction "OUT-_6") (pintype "unspecified"))
      (node (ref "P1") (pin "2") (pinfunction "GND_2") (pintype "unspecified"))
      (node (ref "PZEM") (pin "1") (pinfunction "GND_1") (pintype "unspecified"))
      (node (ref "R1") (pin "2") (pinfunction "2_2") (pintype "input"))
      (node (ref "R2") (pin "2") (pinfunction "2_2") (pintype "input"))
      (node (ref "R3") (pin "2") (pinfunction "2_2") (pintype "input"))
      (node (ref "R4") (pin "2") (pinfunction "2_2") (pintype "input"))
      (node (ref "R5") (pin "2") (pinfunction "2_2") (pintype "input"))
      (node (ref "R6") (pin "2") (pinfunction "2_2") (pintype "input"))
      (node (ref "RE1") (pin "1") (pinfunction "K_1") (pintype "unspecified"))
      (node (ref "RE2") (pin "1") (pinfunction "K_1") (pintype "unspecified"))
      (node (ref "RE3") (pin "1") (pinfunction "K_1") (pintype "unspecified"))
      (node (ref "RE4") (pin "1") (pinfunction "K_1") (pintype "unspecified"))
      (node (ref "RE5") (pin "1") (pinfunction "K_1") (pintype "unspecified"))
      (node (ref "RE6") (pin "1") (pinfunction "K_1") (pintype "unspecified"))
      (node (ref "RE7") (pin "1") (pinfunction "K_1") (pintype "unspecified"))
      (node (ref "RE8") (pin "1") (pinfunction "K_1") (pintype "unspecified"))
      (node (ref "S2") (pin "10") (pinfunction "GND_10") (pintype "unspecified"))
      (node (ref "U$1") (pin "19") (pinfunction "GND_B_19") (pintype "bidirectional"))
      (node (ref "U1") (pin "2") (pinfunction "Cathode_2") (pintype "unspecified"))
      (node (ref "U2") (pin "2") (pinfunction "Cathode_2") (pintype "unspecified"))
      (node (ref "U3") (pin "2") (pinfunction "Cathode_2") (pintype "unspecified"))
      (node (ref "U4") (pin "2") (pinfunction "Cathode_2") (pintype "unspecified"))
      (node (ref "U5") (pin "2") (pinfunction "Cathode_2") (pintype "unspecified"))
      (node (ref "U6") (pin "2") (pinfunction "Cathode_2") (pintype "unspecified"))
      (node (ref "U7") (pin "1") (pinfunction "GND_1") (pintype "unspecified"))
      (node (ref "W1") (pin "12") (pinfunction "GND_12") (pintype "unspecified"))
    )
    (net (code "78") (name "OneW") (class "Default")
      (node (ref "DS18B20_1") (pin "2") (pinfunction "D_2") (pintype "input"))
      (node (ref "DS18B20_2") (pin "2") (pinfunction "D_2") (pintype "input"))
      (node (ref "R20") (pin "2") (pinfunction "2_2") (pintype "input"))
      (node (ref "U$1") (pin "32") (pinfunction "GPIO16_32") (pintype "bidirectional"))
    )
    (net (code "79") (name "RST") (class "Default")
      (node (ref "U$1") (pin "30") (pinfunction "GPIO05_30") (pintype "bidirectional"))
      (node (ref "W1") (pin "8") (pinfunction "RST_8") (pintype "unspecified"))
    )
    (net (code "80") (name "RX") (class "Default")
      (node (ref "PZEM") (pin "2") (pinfunction "TX_2") (pintype "unspecified"))
      (node (ref "U$1") (pin "25") (pinfunction "RX00_25") (pintype "bidirectional"))
      (node (ref "U7") (pin "2") (pinfunction "TX_2") (pintype "unspecified"))
    )
    (net (code "81") (name "SCL") (class "Default")
      (node (ref "I2C_1") (pin "1") (pinfunction "SCL_1") (pintype "unspecified"))
      (node (ref "I2C_2") (pin "1") (pinfunction "SCL_1") (pintype "unspecified"))
      (node (ref "I2C_3") (pin "1") (pinfunction "SCL_1") (pintype "unspecified"))
      (node (ref "I2C_4") (pin "1") (pinfunction "SCL_1") (pintype "unspecified"))
      (node (ref "ISO-EZO") (pin "5") (pinfunction "B_5") (pintype "unspecified"))
      (node (ref "P1") (pin "3") (pinfunction "SCL_3") (pintype "unspecified"))
      (node (ref "R22") (pin "2") (pinfunction "2_2") (pintype "input"))
      (node (ref "S2") (pin "16") (pinfunction "SCL_16") (pintype "unspecified"))
      (node (ref "U$1") (pin "23") (pinfunction "GPIO22_23") (pintype "bidirectional"))
    )
    (net (code "82") (name "SCLK") (class "Default")
      (node (ref "U$1") (pin "31") (pinfunction "GPIO17_31") (pintype "bidirectional"))
      (node (ref "W1") (pin "4") (pinfunction "SCLK_4") (pintype "unspecified"))
    )
    (net (code "83") (name "SDA") (class "Default")
      (node (ref "I2C_1") (pin "2") (pinfunction "SDA_2") (pintype "unspecified"))
      (node (ref "I2C_2") (pin "2") (pinfunction "SDA_2") (pintype "unspecified"))
      (node (ref "I2C_3") (pin "2") (pinfunction "SDA_2") (pintype "unspecified"))
      (node (ref "I2C_4") (pin "2") (pinfunction "SDA_2") (pintype "unspecified"))
      (node (ref "ISO-EZO") (pin "4") (pinfunction "A_4") (pintype "unspecified"))
      (node (ref "P1") (pin "4") (pinfunction "SDA_4") (pintype "unspecified"))
      (node (ref "R21") (pin "2") (pinfunction "2_2") (pintype "input"))
      (node (ref "S2") (pin "15") (pinfunction "SDA_15") (pintype "unspecified"))
      (node (ref "U$1") (pin "36") (pinfunction "GPIO15_36") (pintype "bidirectional"))
    )
    (net (code "84") (name "TX") (class "Default")
      (node (ref "PZEM") (pin "3") (pinfunction "RX_3") (pintype "unspecified"))
      (node (ref "U$1") (pin "24") (pinfunction "TX00_24") (pintype "bidirectional"))
      (node (ref "U7") (pin "3") (pinfunction "RX_3") (pintype "unspecified"))
    )
    (net (code "85") (name "unconnected-(BP_RAZ-VCC-Pad3)") (class "Default")
      (node (ref "BP_RAZ") (pin "3") (pinfunction "VCC_3") (pintype "input"))
    )
    (net (code "86") (name "unconnected-(ISO-EZO-EN-Pad2)") (class "Default")
      (node (ref "ISO-EZO") (pin "2") (pinfunction "EN_2") (pintype "unspecified"))
    )
    (net (code "87") (name "unconnected-(ISO-EZO-N{slash}C-Pad7)") (class "Default")
      (node (ref "ISO-EZO") (pin "7") (pinfunction "N/C_7") (pintype "unspecified"))
    )
    (net (code "88") (name "unconnected-(P1-ADDR-Pad5)") (class "Default")
      (node (ref "P1") (pin "5") (pinfunction "ADDR_5") (pintype "unspecified"))
    )
    (net (code "89") (name "unconnected-(P1-ALRT-Pad6)") (class "Default")
      (node (ref "P1") (pin "6") (pinfunction "ALRT_6") (pintype "unspecified"))
    )
    (net (code "90") (name "unconnected-(S2-3V3-Pad29)") (class "Default")
      (node (ref "S2") (pin "29") (pinfunction "3V3_29") (pintype "unspecified"))
    )
    (net (code "91") (name "unconnected-(S2-GND-Pad13)") (class "Default")
      (node (ref "S2") (pin "13") (pinfunction "GND_13") (pintype "unspecified"))
    )
    (net (code "92") (name "unconnected-(S2-GND-Pad17)") (class "Default")
      (node (ref "S2") (pin "17") (pinfunction "GND_17") (pintype "unspecified"))
    )
    (net (code "93") (name "unconnected-(S2-GND-Pad30)") (class "Default")
      (node (ref "S2") (pin "30") (pinfunction "GND_30") (pintype "unspecified"))
    )
    (net (code "94") (name "unconnected-(S2-INT-Pad11)") (class "Default")
      (node (ref "S2") (pin "11") (pinfunction "INT_11") (pintype "unspecified"))
    )
    (net (code "95") (name "unconnected-(S2-OSC-Pad32)") (class "Default")
      (node (ref "S2") (pin "32") (pinfunction "OSC_32") (pintype "unspecified"))
    )
    (net (code "96") (name "unconnected-(S2-RST-Pad12)") (class "Default")
      (node (ref "S2") (pin "12") (pinfunction "RST_12") (pintype "unspecified"))
    )
    (net (code "97") (name "unconnected-(S2-RST-Pad31)") (class "Default")
      (node (ref "S2") (pin "31") (pinfunction "RST_31") (pintype "unspecified"))
    )
    (net (code "98") (name "unconnected-(S2-SCL-Pad27)") (class "Default")
      (node (ref "S2") (pin "27") (pinfunction "SCL_27") (pintype "unspecified"))
    )
    (net (code "99") (name "unconnected-(S2-SDA-Pad28)") (class "Default")
      (node (ref "S2") (pin "28") (pinfunction "SDA_28") (pintype "unspecified"))
    )
    (net (code "100") (name "unconnected-(S2-VC1-Pad5)") (class "Default")
      (node (ref "S2") (pin "5") (pinfunction "VC1_5") (pintype "unspecified"))
    )
    (net (code "101") (name "unconnected-(S2-VC2-Pad22)") (class "Default")
      (node (ref "S2") (pin "22") (pinfunction "VC2_22") (pintype "unspecified"))
    )
    (net (code "102") (name "unconnected-(SONDE-Pad3)") (class "Default")
      (node (ref "SONDE") (pin "3") (pinfunction "3_3") (pintype "bidirectional"))
    )
    (net (code "103") (name "unconnected-(U$1-3V3_A-Pad1)") (class "Default")
      (node (ref "U$1") (pin "1") (pinfunction "3V3_A_1") (pintype "bidirectional"))
    )
    (net (code "104") (name "unconnected-(U$1-3V3_B-Pad40)") (class "Default")
      (node (ref "U$1") (pin "40") (pinfunction "3V3_B_40") (pintype "bidirectional"))
    )
    (net (code "105") (name "unconnected-(U$1-GND_A-Pad2)") (class "Default")
      (node (ref "U$1") (pin "2") (pinfunction "GND_A_2") (pintype "bidirectional"))
    )
    (net (code "106") (name "unconnected-(U$1-GND_C-Pad21)") (class "Default")
      (node (ref "U$1") (pin "21") (pinfunction "GND_C_21") (pintype "bidirectional"))
    )
    (net (code "107") (name "unconnected-(U$1-GND_D-Pad27)") (class "Default")
      (node (ref "U$1") (pin "27") (pinfunction "GND_D_27") (pintype "bidirectional"))
    )
    (net (code "108") (name "unconnected-(U$1-GPIO00-Pad34)") (class "Default")
      (node (ref "U$1") (pin "34") (pinfunction "GPIO00_34") (pintype "bidirectional"))
    )
    (net (code "109") (name "unconnected-(U$1-GPIO02-Pad35)") (class "Default")
      (node (ref "U$1") (pin "35") (pinfunction "GPIO02_35") (pintype "bidirectional"))
    )
    (net (code "110") (name "unconnected-(U$1-GPIO06-Pad39)") (class "Default")
      (node (ref "U$1") (pin "39") (pinfunction "GPIO06_39") (pintype "bidirectional"))
    )
    (net (code "111") (name "unconnected-(U$1-GPIO07-Pad38)") (class "Default")
      (node (ref "U$1") (pin "38") (pinfunction "GPIO07_38") (pintype "bidirectional"))
    )
    (net (code "112") (name "unconnected-(U$1-GPIO08-Pad37)") (class "Default")
      (node (ref "U$1") (pin "37") (pinfunction "GPIO08_37") (pintype "bidirectional"))
    )
    (net (code "113") (name "unconnected-(U$1-GPIO9-Pad15)") (class "Default")
      (node (ref "U$1") (pin "15") (pinfunction "GPIO9_15") (pintype "bidirectional"))
    )
    (net (code "114") (name "unconnected-(U$1-GPIO10-Pad18)") (class "Default")
      (node (ref "U$1") (pin "18") (pinfunction "GPIO10_18") (pintype "bidirectional"))
    )
    (net (code "115") (name "unconnected-(U$1-GPIO11-Pad17)") (class "Default")
      (node (ref "U$1") (pin "17") (pinfunction "GPIO11_17") (pintype "bidirectional"))
    )
    (net (code "116") (name "unconnected-(U$1-GPIO23-Pad22)") (class "Default")
      (node (ref "U$1") (pin "22") (pinfunction "GPIO23_22") (pintype "bidirectional"))
    )
    (net (code "117") (name "unconnected-(U7-AC-Pad7)") (class "Default")
      (node (ref "U7") (pin "7") (pinfunction "AC_7") (pintype "unspecified"))
    )
    (net (code "118") (name "unconnected-(U7-AC-Pad8)") (class "Default")
      (node (ref "U7") (pin "8") (pinfunction "AC_8") (pintype "unspecified"))
    )
    (net (code "119") (name "unconnected-(U7-CT-Pad5)") (class "Default")
      (node (ref "U7") (pin "5") (pinfunction "CT_5") (pintype "unspecified"))
    )
    (net (code "120") (name "unconnected-(U7-CT-Pad6)") (class "Default")
      (node (ref "U7") (pin "6") (pinfunction "CT_6") (pintype "unspecified"))
    )
    (net (code "121") (name "unconnected-(U8-Pad1)") (class "Default")
      (node (ref "U8") (pin "1") (pinfunction "1_1") (pintype "unspecified"))
    )
    (net (code "122") (name "unconnected-(U8-Pad2)") (class "Default")
      (node (ref "U8") (pin "2") (pinfunction "2_2") (pintype "unspecified"))
    )
    (net (code "123") (name "unconnected-(W1-3V3-Pad10)") (class "Default")
      (node (ref "W1") (pin "10") (pinfunction "3V3_10") (pintype "unspecified"))
    )
    (net (code "124") (name "unconnected-(W1-GND-Pad1)") (class "Default")
      (node (ref "W1") (pin "1") (pinfunction "GND_1") (pintype "unspecified"))
    )
    (net (code "125") (name "unconnected-(W1-GND-Pad2)") (class "Default")
      (node (ref "W1") (pin "2") (pinfunction "GND_2") (pintype "unspecified"))
    )
    (net (code "126") (name "unconnected-(W1-NC-Pad9)") (class "Default")
      (node (ref "W1") (pin "9") (pinfunction "NC_9") (pintype "unspecified"))
    )
  )
)
